# main.net
KiCad netlist of a schematic drawn in EAGLE
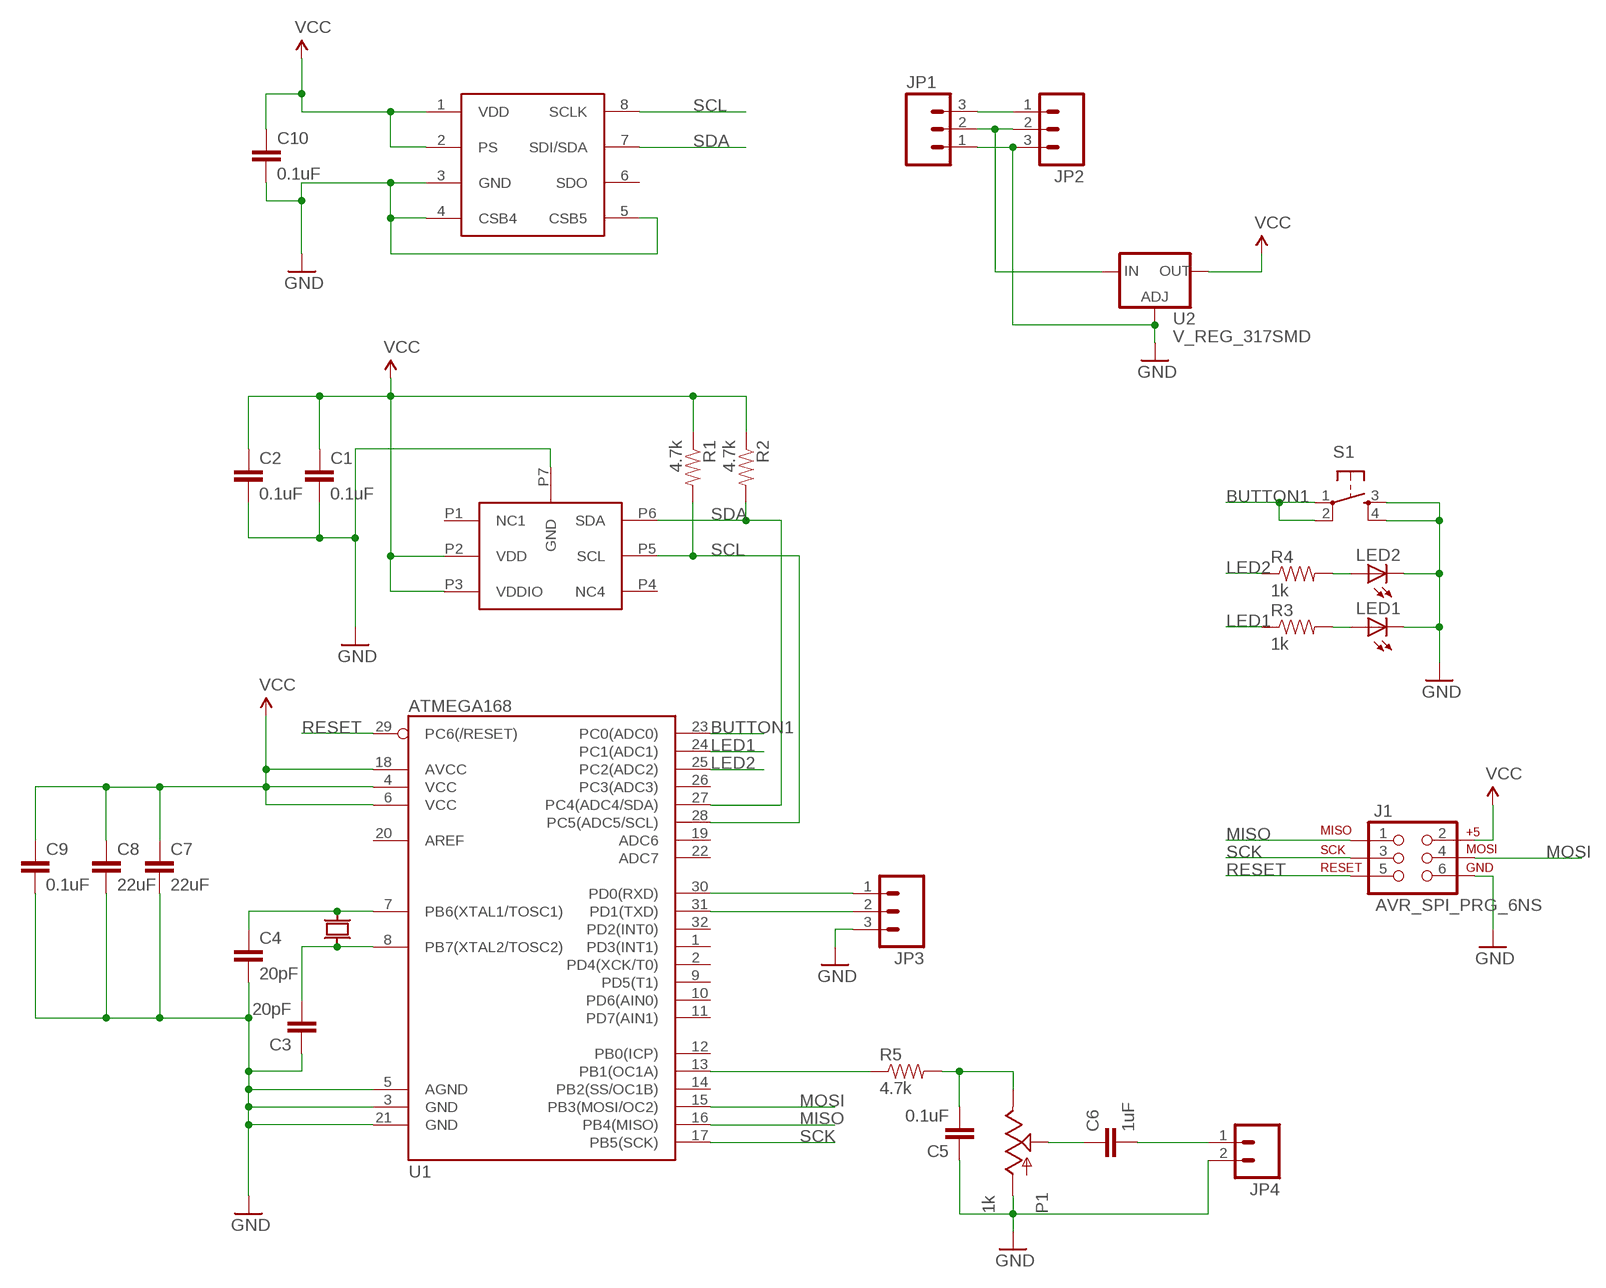
[diagram p0: schematic, sheet 1]

(export (version "E")
  (design (tool "Eeschema 10.0.6"))
  (components
    (comp (ref "C1")
      (value "0.1uF")
      (footprint "eagle-import:0603-CAP")
      (libsource (lib "eagle-import") (part "CAP0603-CAP"))
    )
    (comp (ref "C2")
      (value "0.1uF")
      (footprint "eagle-import:0603-CAP")
      (libsource (lib "eagle-import") (part "CAP0603-CAP"))
    )
    (comp (ref "C3")
      (value "20pF")
      (footprint "eagle-import:0603-CAP")
      (libsource (lib "eagle-import") (part "CAP0603-CAP"))
    )
    (comp (ref "C4")
      (value "20pF")
      (footprint "eagle-import:0603-CAP")
      (libsource (lib "eagle-import") (part "CAP0603-CAP"))
    )
    (comp (ref "C5")
      (value "0.1uF")
      (footprint "eagle-import:0603-CAP")
      (libsource (lib "eagle-import") (part "CAP0603-CAP"))
    )
    (comp (ref "C6")
      (value "1uF")
      (footprint "eagle-import:0603-CAP")
      (libsource (lib "eagle-import") (part "CAP0603-CAP"))
    )
    (comp (ref "C7")
      (value "22uF")
      (footprint "eagle-import:0805")
      (libsource (lib "eagle-import") (part "CAP0805"))
    )
    (comp (ref "C8")
      (value "22uF")
      (footprint "eagle-import:0805")
      (libsource (lib "eagle-import") (part "CAP0805"))
    )
    (comp (ref "C9")
      (value "0.1uF")
      (footprint "eagle-import:0603-CAP")
      (libsource (lib "eagle-import") (part "CAP0603-CAP"))
    )
    (comp (ref "C10")
      (value "0.1uF")
      (footprint "eagle-import:0603-CAP")
      (libsource (lib "eagle-import") (part "CAP0603-CAP"))
    )
    (comp (ref "J1")
      (value "AVR_SPI_PRG_6NS")
      (footprint "eagle-import:2X3-NS")
      (libsource (lib "eagle-import") (part "AVR_SPI_PRG_6NS"))
    )
    (comp (ref "JP1")
      (value "M03PTH")
      (footprint "eagle-import:1X03")
      (libsource (lib "eagle-import") (part "M03PTH"))
    )
    (comp (ref "JP2")
      (value "M03PTH")
      (footprint "eagle-import:1X03")
      (libsource (lib "eagle-import") (part "M03PTH"))
    )
    (comp (ref "JP3")
      (value "M03PTH")
      (footprint "eagle-import:1X03")
      (libsource (lib "eagle-import") (part "M03PTH"))
    )
    (comp (ref "JP4")
      (value "M02PTH")
      (footprint "eagle-import:1X02")
      (libsource (lib "eagle-import") (part "M02PTH"))
    )
    (comp (ref "LED1")
      (value "LED0603")
      (footprint "eagle-import:LED-0603")
      (libsource (lib "eagle-import") (part "LED0603"))
    )
    (comp (ref "LED2")
      (value "LED0603")
      (footprint "eagle-import:LED-0603")
      (libsource (lib "eagle-import") (part "LED0603"))
    )
    (comp (ref "P1")
      (value "1k")
      (footprint "eagle-import:TRIM_POT")
      (libsource (lib "eagle-import") (part "POTTRIM"))
    )
    (comp (ref "R1")
      (value "4.7k")
      (footprint "eagle-import:0603-RES")
      (libsource (lib "eagle-import") (part "RESISTOR0603-RES"))
    )
    (comp (ref "R2")
      (value "4.7k")
      (footprint "eagle-import:0603-RES")
      (libsource (lib "eagle-import") (part "RESISTOR0603-RES"))
    )
    (comp (ref "R3")
      (value "1k")
      (footprint "eagle-import:0603-RES")
      (libsource (lib "eagle-import") (part "RESISTOR0603-RES"))
    )
    (comp (ref "R4")
      (value "1k")
      (footprint "eagle-import:0603-RES")
      (libsource (lib "eagle-import") (part "RESISTOR0603-RES"))
    )
    (comp (ref "R5")
      (value "4.7k")
      (footprint "eagle-import:0603-RES")
      (libsource (lib "eagle-import") (part "RESISTOR0603-RES"))
    )
    (comp (ref "S1")
      (value "TAC_SWITCHSMD")
      (footprint "eagle-import:TACTILE_SWITCH_SMD")
      (libsource (lib "eagle-import") (part "TAC_SWITCHSMD"))
    )
    (comp (ref "U$1")
      (value "BMP180")
      (footprint "eagle-import:BMP180")
      (libsource (lib "eagle-import") (part "BMP180"))
    )
    (comp (ref "U$2")
      (value "MS5611")
      (footprint "eagle-import:MS5611")
      (libsource (lib "eagle-import") (part "MS5611"))
    )
    (comp (ref "U$3")
      (value "16M")
      (footprint "eagle-import:HC49_US_7X4")
      (libsource (lib "eagle-import") (part "CRYSTAL"))
    )
    (comp (ref "U1")
      (value "ATMEGA168")
      (footprint "eagle-import:TQFP32-08")
      (libsource (lib "eagle-import") (part "ATMEGA168"))
    )
    (comp (ref "U2")
      (value "V_REG_317SMD")
      (footprint "eagle-import:SOT223")
      (libsource (lib "eagle-import") (part "V_REG_317SMD"))
    )
  )
  (nets
    (net (code "1") (name "/BUTTON1") (class "Default")
      (node (ref "S1") (pin "1") (pinfunction "1_1") (pintype "passive"))
      (node (ref "S1") (pin "2") (pinfunction "2_2") (pintype "passive"))
      (node (ref "U1") (pin "23") (pinfunction "PC0(ADC0)_23") (pintype "bidirectional"))
    )
    (net (code "2") (name "/LED1") (class "Default")
      (node (ref "R3") (pin "1") (pinfunction "1_1") (pintype "passive"))
      (node (ref "U1") (pin "24") (pinfunction "PC1(ADC1)_24") (pintype "bidirectional"))
    )
    (net (code "3") (name "/LED2") (class "Default")
      (node (ref "R4") (pin "1") (pinfunction "1_1") (pintype "passive"))
      (node (ref "U1") (pin "25") (pinfunction "PC2(ADC2)_25") (pintype "bidirectional"))
    )
    (net (code "4") (name "/MISO") (class "Default")
      (node (ref "J1") (pin "1") (pinfunction "1_1") (pintype "passive"))
      (node (ref "U1") (pin "16") (pinfunction "PB4(MISO)_16") (pintype "bidirectional"))
    )
    (net (code "5") (name "/MOSI") (class "Default")
      (node (ref "J1") (pin "4") (pinfunction "4_4") (pintype "passive"))
      (node (ref "U1") (pin "15") (pinfunction "PB3(MOSI/OC2)_15") (pintype "bidirectional"))
    )
    (net (code "6") (name "/RESET") (class "Default")
      (node (ref "J1") (pin "5") (pinfunction "5_5") (pintype "passive"))
      (node (ref "U1") (pin "29") (pinfunction "PC6(/RESET)_29") (pintype "bidirectional"))
    )
    (net (code "7") (name "/SCK") (class "Default")
      (node (ref "J1") (pin "3") (pinfunction "3_3") (pintype "passive"))
      (node (ref "U1") (pin "17") (pinfunction "PB5(SCK)_17") (pintype "bidirectional"))
    )
    (net (code "8") (name "/SCL") (class "Default")
      (node (ref "R1") (pin "2") (pinfunction "2_2") (pintype "passive"))
      (node (ref "U$1") (pin "P5") (pinfunction "SCL_P5") (pintype "bidirectional"))
      (node (ref "U$2") (pin "8") (pinfunction "SCLK_8") (pintype "bidirectional"))
      (node (ref "U1") (pin "28") (pinfunction "PC5(ADC5/SCL)_28") (pintype "bidirectional"))
    )
    (net (code "9") (name "/SDA") (class "Default")
      (node (ref "R2") (pin "2") (pinfunction "2_2") (pintype "passive"))
      (node (ref "U$1") (pin "P6") (pinfunction "SDA_P6") (pintype "bidirectional"))
      (node (ref "U$2") (pin "7") (pinfunction "SDI/SDA_7") (pintype "bidirectional"))
      (node (ref "U1") (pin "27") (pinfunction "PC4(ADC4/SDA)_27") (pintype "bidirectional"))
    )
    (net (code "10") (name "GND") (class "Default")
      (node (ref "C1") (pin "2") (pinfunction "2_2") (pintype "passive"))
      (node (ref "C10") (pin "2") (pinfunction "2_2") (pintype "passive"))
      (node (ref "C2") (pin "2") (pinfunction "2_2") (pintype "passive"))
      (node (ref "C3") (pin "1") (pinfunction "1_1") (pintype "passive"))
      (node (ref "C4") (pin "2") (pinfunction "2_2") (pintype "passive"))
      (node (ref "C5") (pin "1") (pinfunction "1_1") (pintype "passive"))
      (node (ref "C7") (pin "2") (pinfunction "2_2") (pintype "passive"))
      (node (ref "C8") (pin "2") (pinfunction "2_2") (pintype "passive"))
      (node (ref "C9") (pin "2") (pinfunction "2_2") (pintype "passive"))
      (node (ref "J1") (pin "6") (pinfunction "6_6") (pintype "passive"))
      (node (ref "JP1") (pin "1") (pinfunction "1_1") (pintype "passive"))
      (node (ref "JP2") (pin "3") (pinfunction "3_3") (pintype "passive"))
      (node (ref "JP3") (pin "3") (pinfunction "3_3") (pintype "passive"))
      (node (ref "JP4") (pin "2") (pinfunction "2_2") (pintype "passive"))
      (node (ref "LED1") (pin "C") (pinfunction "C_C") (pintype "passive"))
      (node (ref "LED2") (pin "C") (pinfunction "C_C") (pintype "passive"))
      (node (ref "P1") (pin "3") (pinfunction "A_3") (pintype "passive"))
      (node (ref "S1") (pin "3") (pinfunction "3_3") (pintype "passive"))
      (node (ref "S1") (pin "4") (pinfunction "4_4") (pintype "passive"))
      (node (ref "U$1") (pin "P7") (pinfunction "GND_P7") (pintype "bidirectional"))
      (node (ref "U$2") (pin "3") (pinfunction "GND_3") (pintype "bidirectional"))
      (node (ref "U$2") (pin "4") (pinfunction "CSB4_4") (pintype "bidirectional"))
      (node (ref "U$2") (pin "5") (pinfunction "CSB5_5") (pintype "bidirectional"))
      (node (ref "U1") (pin "21") (pinfunction "GND_21") (pintype "bidirectional"))
      (node (ref "U1") (pin "3") (pinfunction "GND_3") (pintype "bidirectional"))
      (node (ref "U1") (pin "5") (pinfunction "AGND_5") (pintype "bidirectional"))
      (node (ref "U2") (pin "1") (pinfunction "ADJ_1") (pintype "input"))
    )
    (net (code "11") (name "Net-(C6-Pad2)") (class "Default")
      (node (ref "C6") (pin "2") (pinfunction "2_2") (pintype "passive"))
      (node (ref "JP4") (pin "1") (pinfunction "1_1") (pintype "passive"))
    )
    (net (code "12") (name "Net-(JP1-Pad3)") (class "Default")
      (node (ref "JP1") (pin "3") (pinfunction "3_3") (pintype "passive"))
      (node (ref "JP2") (pin "1") (pinfunction "1_1") (pintype "passive"))
    )
    (net (code "13") (name "Net-(LED1-PadA)") (class "Default")
      (node (ref "LED1") (pin "A") (pinfunction "A_A") (pintype "passive"))
      (node (ref "R3") (pin "2") (pinfunction "2_2") (pintype "passive"))
    )
    (net (code "14") (name "Net-(LED2-PadA)") (class "Default")
      (node (ref "LED2") (pin "A") (pinfunction "A_A") (pintype "passive"))
      (node (ref "R4") (pin "2") (pinfunction "2_2") (pintype "passive"))
    )
    (net (code "15") (name "Net-(P1-E)") (class "Default")
      (node (ref "C5") (pin "2") (pinfunction "2_2") (pintype "passive"))
      (node (ref "P1") (pin "2") (pinfunction "E_2") (pintype "passive"))
      (node (ref "R5") (pin "2") (pinfunction "2_2") (pintype "passive"))
    )
    (net (code "16") (name "Net-(P1-S)") (class "Default")
      (node (ref "C6") (pin "1") (pinfunction "1_1") (pintype "passive"))
      (node (ref "P1") (pin "1") (pinfunction "S_1") (pintype "passive"))
    )
    (net (code "17") (name "Net-(U1-PB1(OC1A))") (class "Default")
      (node (ref "R5") (pin "1") (pinfunction "1_1") (pintype "passive"))
      (node (ref "U1") (pin "13") (pinfunction "PB1(OC1A)_13") (pintype "bidirectional"))
    )
    (net (code "18") (name "Net-(U1-PB6(XTAL1{slash}TOSC1))") (class "Default")
      (node (ref "C4") (pin "1") (pinfunction "1_1") (pintype "passive"))
      (node (ref "U$3") (pin "P2") (pinfunction "P2_P2") (pintype "bidirectional"))
      (node (ref "U1") (pin "7") (pinfunction "PB6(XTAL1/TOSC1)_7") (pintype "bidirectional"))
    )
    (net (code "19") (name "Net-(U1-PB7(XTAL2{slash}TOSC2))") (class "Default")
      (node (ref "C3") (pin "2") (pinfunction "2_2") (pintype "passive"))
      (node (ref "U$3") (pin "P1") (pinfunction "P1_P1") (pintype "bidirectional"))
      (node (ref "U1") (pin "8") (pinfunction "PB7(XTAL2/TOSC2)_8") (pintype "bidirectional"))
    )
    (net (code "20") (name "Net-(U1-PD0(RXD))") (class "Default")
      (node (ref "JP3") (pin "1") (pinfunction "1_1") (pintype "passive"))
      (node (ref "U1") (pin "30") (pinfunction "PD0(RXD)_30") (pintype "bidirectional"))
    )
    (net (code "21") (name "Net-(U1-PD1(TXD))") (class "Default")
      (node (ref "JP3") (pin "2") (pinfunction "2_2") (pintype "passive"))
      (node (ref "U1") (pin "31") (pinfunction "PD1(TXD)_31") (pintype "bidirectional"))
    )
    (net (code "22") (name "Net-(U2-IN)") (class "Default")
      (node (ref "JP1") (pin "2") (pinfunction "2_2") (pintype "passive"))
      (node (ref "JP2") (pin "2") (pinfunction "2_2") (pintype "passive"))
      (node (ref "U2") (pin "3") (pinfunction "IN_3") (pintype "input"))
    )
    (net (code "23") (name "VCC") (class "Default")
      (node (ref "C1") (pin "1") (pinfunction "1_1") (pintype "passive"))
      (node (ref "C10") (pin "1") (pinfunction "1_1") (pintype "passive"))
      (node (ref "C2") (pin "1") (pinfunction "1_1") (pintype "passive"))
      (node (ref "C7") (pin "1") (pinfunction "1_1") (pintype "passive"))
      (node (ref "C8") (pin "1") (pinfunction "1_1") (pintype "passive"))
      (node (ref "C9") (pin "1") (pinfunction "1_1") (pintype "passive"))
      (node (ref "J1") (pin "2") (pinfunction "2_2") (pintype "passive"))
      (node (ref "R1") (pin "1") (pinfunction "1_1") (pintype "passive"))
      (node (ref "R2") (pin "1") (pinfunction "1_1") (pintype "passive"))
      (node (ref "U$1") (pin "P2") (pinfunction "VDD_P2") (pintype "bidirectional"))
      (node (ref "U$1") (pin "P3") (pinfunction "VDDIO_P3") (pintype "bidirectional"))
      (node (ref "U$2") (pin "1") (pinfunction "VDD_1") (pintype "bidirectional"))
      (node (ref "U$2") (pin "2") (pinfunction "PS_2") (pintype "bidirectional"))
      (node (ref "U1") (pin "18") (pinfunction "AVCC_18") (pintype "bidirectional"))
      (node (ref "U1") (pin "4") (pinfunction "VCC_4") (pintype "bidirectional"))
      (node (ref "U1") (pin "6") (pinfunction "VCC_6") (pintype "bidirectional"))
      (node (ref "U2") (pin "2") (pinfunction "OUT_2") (pintype "output"))
    )
    (net (code "24") (name "unconnected-(U$1-NC1-PadP1)") (class "Default")
      (node (ref "U$1") (pin "P1") (pinfunction "NC1_P1") (pintype "bidirectional"))
    )
    (net (code "25") (name "unconnected-(U$1-NC4-PadP4)") (class "Default")
      (node (ref "U$1") (pin "P4") (pinfunction "NC4_P4") (pintype "bidirectional"))
    )
    (net (code "26") (name "unconnected-(U$2-SDO-Pad6)") (class "Default")
      (node (ref "U$2") (pin "6") (pinfunction "SDO_6") (pintype "bidirectional"))
    )
    (net (code "27") (name "unconnected-(U1-ADC6-Pad19)") (class "Default")
      (node (ref "U1") (pin "19") (pinfunction "ADC6_19") (pintype "bidirectional"))
    )
    (net (code "28") (name "unconnected-(U1-ADC7-Pad22)") (class "Default")
      (node (ref "U1") (pin "22") (pinfunction "ADC7_22") (pintype "bidirectional"))
    )
    (net (code "29") (name "unconnected-(U1-AREF-Pad20)") (class "Default")
      (node (ref "U1") (pin "20") (pinfunction "AREF_20") (pintype "bidirectional"))
    )
    (net (code "30") (name "unconnected-(U1-PB0(ICP)-Pad12)") (class "Default")
      (node (ref "U1") (pin "12") (pinfunction "PB0(ICP)_12") (pintype "bidirectional"))
    )
    (net (code "31") (name "unconnected-(U1-PB2(SS{slash}OC1B)-Pad14)") (class "Default")
      (node (ref "U1") (pin "14") (pinfunction "PB2(SS/OC1B)_14") (pintype "bidirectional"))
    )
    (net (code "32") (name "unconnected-(U1-PC3(ADC3)-Pad26)") (class "Default")
      (node (ref "U1") (pin "26") (pinfunction "PC3(ADC3)_26") (pintype "bidirectional"))
    )
    (net (code "33") (name "unconnected-(U1-PD2(INT0)-Pad32)") (class "Default")
      (node (ref "U1") (pin "32") (pinfunction "PD2(INT0)_32") (pintype "bidirectional"))
    )
    (net (code "34") (name "unconnected-(U1-PD3(INT1)-Pad1)") (class "Default")
      (node (ref "U1") (pin "1") (pinfunction "PD3(INT1)_1") (pintype "bidirectional"))
    )
    (net (code "35") (name "unconnected-(U1-PD4(XCK{slash}T0)-Pad2)") (class "Default")
      (node (ref "U1") (pin "2") (pinfunction "PD4(XCK/T0)_2") (pintype "bidirectional"))
    )
    (net (code "36") (name "unconnected-(U1-PD5(T1)-Pad9)") (class "Default")
      (node (ref "U1") (pin "9") (pinfunction "PD5(T1)_9") (pintype "bidirectional"))
    )
    (net (code "37") (name "unconnected-(U1-PD6(AIN0)-Pad10)") (class "Default")
      (node (ref "U1") (pin "10") (pinfunction "PD6(AIN0)_10") (pintype "bidirectional"))
    )
    (net (code "38") (name "unconnected-(U1-PD7(AIN1)-Pad11)") (class "Default")
      (node (ref "U1") (pin "11") (pinfunction "PD7(AIN1)_11") (pintype "bidirectional"))
    )
  )
)
